# V3_TTL.net
KiCad netlist of a schematic drawn in Altium Designer
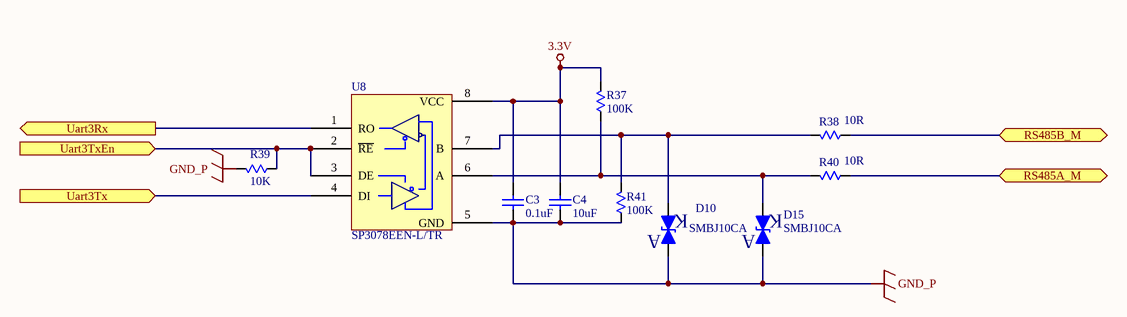
[diagram p0: 海关全向本体电路板V3_TTL通信.SchDoc]

(export (version "E")
  (design (tool "Eeschema 10.0.6"))
  (components
    (comp (ref "C3")
      (value "0.1uF")
      (footprint "C0603-S")
      (description "CAP")
      (fields (field (name "PUBLISHER") "Altium Limited"))
      (libsource (lib "Passive Components Class") (part "CAP"))
    )
    (comp (ref "C4")
      (value "10uF")
      (footprint "C0603-S")
      (description "CAP")
      (fields (field (name "PUBLISHER") "Altium Limited"))
      (libsource (lib "Passive Components Class") (part "CAP"))
    )
    (comp (ref "D10")
      (value "SMBJ10CA")
      (footprint "UPTECH-贴片元件:SMB-S")
      (libsource (lib "MhSchlib") (part "BS0300N"))
    )
    (comp (ref "D15")
      (value "SMBJ10CA")
      (footprint "UPTECH-贴片元件:SMB-S")
      (libsource (lib "MhSchlib") (part "BS0300N"))
    )
    (comp (ref "R37")
      (value "100K")
      (footprint "R0603-S")
      (description "Resistor")
      (fields (field (name "PUBLISHER") "Altium Limited"))
      (libsource (lib "Passive Components Class") (part "RES"))
    )
    (comp (ref "R38")
      (value "10R")
      (footprint "R1206-S")
      (description "Resistor")
      (fields (field (name "PUBLISHER") "Altium Limited"))
      (libsource (lib "") (part "RES_1"))
    )
    (comp (ref "R39")
      (value "10K")
      (footprint "R0603-S")
      (description "Resistor")
      (fields (field (name "PUBLISHER") "Altium Limited"))
      (libsource (lib "") (part "RES_1"))
    )
    (comp (ref "R40")
      (value "10R")
      (footprint "R1206-S")
      (description "Resistor")
      (fields (field (name "PUBLISHER") "Altium Limited"))
      (libsource (lib "") (part "RES_1"))
    )
    (comp (ref "R41")
      (value "100K")
      (footprint "R0603-S")
      (description "Resistor")
      (fields (field (name "PUBLISHER") "Altium Limited"))
      (libsource (lib "Passive Components Class") (part "RES"))
    )
    (comp (ref "U8")
      (value "SP3078EEN-L/TR")
      (footprint "SO8-150")
      (libsource (lib "Interface Class") (part "SP3078EEN"))
    )
  )
  (nets
    (net (code "1") (name "/RS485A_M") (class "Default")
      (node (ref "R40") (pin "1") (pinfunction "1_1") (pintype "passive"))
    )
    (net (code "2") (name "/RS485B_M") (class "Default")
      (node (ref "R38") (pin "1") (pinfunction "1_1") (pintype "passive"))
    )
    (net (code "3") (name "/Uart3Rx") (class "Default")
      (node (ref "U8") (pin "1") (pinfunction "RO_1") (pintype "passive"))
    )
    (net (code "4") (name "/Uart3Tx") (class "Default")
      (node (ref "U8") (pin "4") (pinfunction "DI_4") (pintype "passive"))
    )
    (net (code "5") (name "/Uart3TxEn") (class "Default")
      (node (ref "R39") (pin "1") (pinfunction "1_1") (pintype "passive"))
      (node (ref "U8") (pin "2") (pinfunction "~{RE}_2") (pintype "passive"))
      (node (ref "U8") (pin "3") (pinfunction "DE_3") (pintype "passive"))
    )
    (net (code "6") (name "3.3V") (class "Default")
      (node (ref "C3") (pin "2") (pinfunction "2_2") (pintype "passive"))
      (node (ref "C4") (pin "2") (pinfunction "2_2") (pintype "passive"))
      (node (ref "R37") (pin "2") (pinfunction "2_2") (pintype "passive"))
      (node (ref "U8") (pin "8") (pinfunction "VCC_8") (pintype "passive"))
    )
    (net (code "7") (name "GND_P") (class "Default")
      (node (ref "C3") (pin "1") (pinfunction "1_1") (pintype "passive"))
      (node (ref "C4") (pin "1") (pinfunction "1_1") (pintype "passive"))
      (node (ref "D10") (pin "1") (pinfunction "A_1") (pintype "passive"))
      (node (ref "D15") (pin "1") (pinfunction "A_1") (pintype "passive"))
      (node (ref "R39") (pin "2") (pinfunction "2_2") (pintype "passive"))
      (node (ref "R41") (pin "1") (pinfunction "1_1") (pintype "passive"))
      (node (ref "U8") (pin "5") (pinfunction "GND_5") (pintype "passive"))
    )
    (net (code "8") (name "Net-(D10-K)") (class "Default")
      (node (ref "D10") (pin "2") (pinfunction "K_2") (pintype "passive"))
      (node (ref "R38") (pin "2") (pinfunction "2_2") (pintype "passive"))
      (node (ref "R41") (pin "2") (pinfunction "2_2") (pintype "passive"))
      (node (ref "U8") (pin "7") (pinfunction "B_7") (pintype "passive"))
    )
    (net (code "9") (name "Net-(D15-K)") (class "Default")
      (node (ref "D15") (pin "2") (pinfunction "K_2") (pintype "passive"))
      (node (ref "R37") (pin "1") (pinfunction "1_1") (pintype "passive"))
      (node (ref "R40") (pin "2") (pinfunction "2_2") (pintype "passive"))
      (node (ref "U8") (pin "6") (pinfunction "A_6") (pintype "passive"))
    )
  )
)
